# MCU_STM32L051.net
KiCad netlist of a schematic drawn in Altium Designer
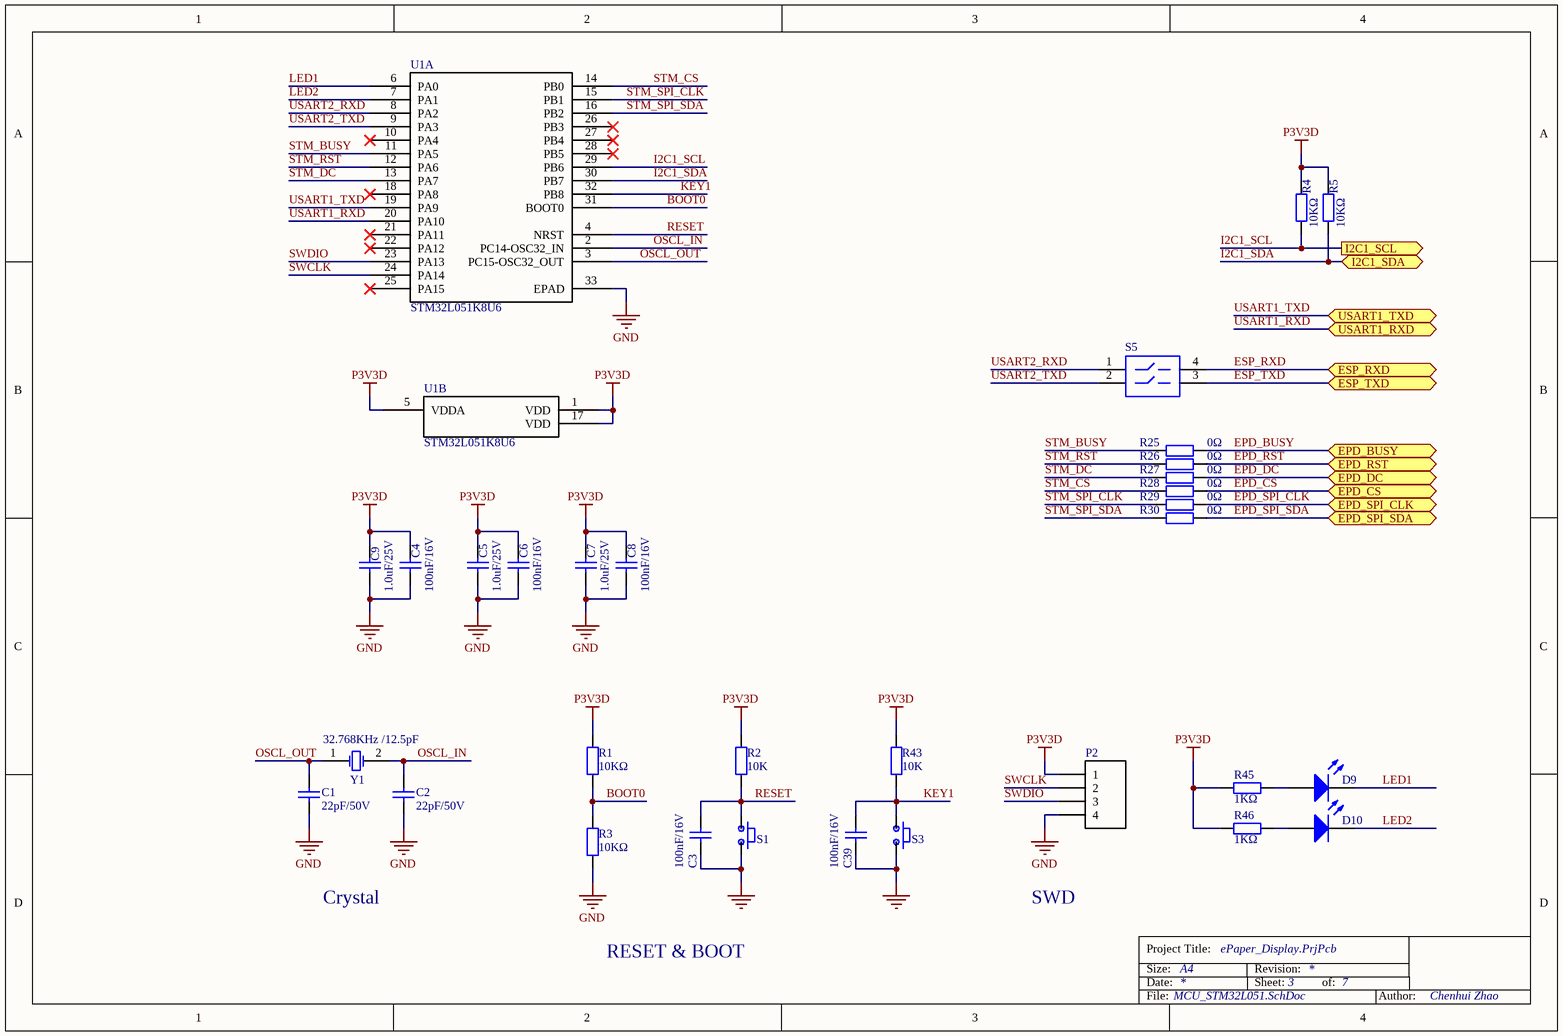
[diagram p0: MCU_STM32L051.SchDoc]

(export (version "E")
  (design (tool "Eeschema 10.0.6"))
  (components
    (comp (ref "C1")
      (value "22pF/50V")
      (footprint "0402_C")
      (description "贴片电容")
      (libsource (lib "Miscellaneous Devices LC") (part "0402 22pF (220) 5% 50V"))
    )
    (comp (ref "C2")
      (value "22pF/50V")
      (footprint "0402_C")
      (description "贴片电容")
      (libsource (lib "Miscellaneous Devices LC") (part "0402 22pF (220) 5% 50V"))
    )
    (comp (ref "C3")
      (value "100nF/16V")
      (footprint "0402_C")
      (description "贴片电容")
      (libsource (lib "Miscellaneous Devices LC") (part "0402 100nF (104) 10% 16V"))
    )
    (comp (ref "C4")
      (value "100nF/16V")
      (footprint "0402_C")
      (description "贴片电容")
      (libsource (lib "Miscellaneous Devices LC") (part "0402 100nF (104) 10% 16V"))
    )
    (comp (ref "C5")
      (value "1.0uF/25V")
      (footprint "0402_C")
      (description "贴片电容")
      (libsource (lib "Miscellaneous Devices LC") (part "0402 1.0uF (105) 10% 25V"))
    )
    (comp (ref "C6")
      (value "100nF/16V")
      (footprint "0402_C")
      (description "贴片电容")
      (libsource (lib "Miscellaneous Devices LC") (part "0402 100nF (104) 10% 16V"))
    )
    (comp (ref "C7")
      (value "1.0uF/25V")
      (footprint "0402_C")
      (description "贴片电容")
      (libsource (lib "Miscellaneous Devices LC") (part "0402 1.0uF (105) 10% 25V"))
    )
    (comp (ref "C8")
      (value "100nF/16V")
      (footprint "0402_C")
      (description "贴片电容")
      (libsource (lib "Miscellaneous Devices LC") (part "0402 100nF (104) 10% 16V"))
    )
    (comp (ref "C9")
      (value "1.0uF/25V")
      (footprint "0402_C")
      (description "贴片电容")
      (libsource (lib "Miscellaneous Devices LC") (part "0402 1.0uF (105) 10% 25V"))
    )
    (comp (ref "C39")
      (value "100nF/16V")
      (footprint "0402_C")
      (description "贴片电容")
      (libsource (lib "Miscellaneous Devices LC") (part "0402 100nF (104) 10% 16V"))
    )
    (comp (ref "D9")
      (value "蓝灯 0603")
      (footprint "0603_LED_S1")
      (description "发光二极管")
      (libsource (lib "Miscellaneous Devices LC") (part "0603 蓝灯"))
    )
    (comp (ref "D10")
      (value "蓝灯 0603")
      (footprint "0603_LED_S1")
      (description "发光二极管")
      (libsource (lib "Miscellaneous Devices LC") (part "0603 蓝灯"))
    )
    (comp (ref "P2")
      (value "Header 4")
      (footprint "DIP4-2.00")
      (description "Header, 4-Pin")
      (fields (field (name "PUBLISHER") "Altium Limited"))
      (libsource (lib "Connectors") (part "Header 4"))
    )
    (comp (ref "R1")
      (value "10KΩ")
      (footprint "0402_R")
      (description "贴片电阻")
      (libsource (lib "Miscellaneous Devices LC") (part "0402 10KΩ (1002) 1%"))
    )
    (comp (ref "R2")
      (value "10K")
      (footprint "0402_R")
      (description "贴片电阻")
      (libsource (lib "Miscellaneous Devices LC") (part "0402 10KΩ (1002) 1%"))
    )
    (comp (ref "R3")
      (value "10KΩ")
      (footprint "0402_R")
      (description "贴片电阻")
      (libsource (lib "Miscellaneous Devices LC") (part "0402 10KΩ (1002) 1%"))
    )
    (comp (ref "R4")
      (value "10KΩ")
      (footprint "0402_R")
      (description "贴片电阻")
      (libsource (lib "Miscellaneous Devices LC") (part "0402 10KΩ (1002) 1%"))
    )
    (comp (ref "R5")
      (value "10KΩ")
      (footprint "0402_R")
      (description "贴片电阻")
      (libsource (lib "Miscellaneous Devices LC") (part "0402 10KΩ (1002) 1%"))
    )
    (comp (ref "R25")
      (value "0Ω")
      (footprint "0402_R")
      (description "贴片电阻")
      (libsource (lib "Miscellaneous Devices LC") (part "0402 0Ω (0R0) 1%"))
    )
    (comp (ref "R26")
      (value "0Ω")
      (footprint "0402_R")
      (description "贴片电阻")
      (libsource (lib "Miscellaneous Devices LC") (part "0402 0Ω (0R0) 1%"))
    )
    (comp (ref "R27")
      (value "0Ω")
      (footprint "0402_R")
      (description "贴片电阻")
      (libsource (lib "Miscellaneous Devices LC") (part "0402 0Ω (0R0) 1%"))
    )
    (comp (ref "R28")
      (value "0Ω")
      (footprint "0402_R")
      (description "贴片电阻")
      (libsource (lib "Miscellaneous Devices LC") (part "0402 0Ω (0R0) 1%"))
    )
    (comp (ref "R29")
      (value "0Ω")
      (footprint "0402_R")
      (description "贴片电阻")
      (libsource (lib "Miscellaneous Devices LC") (part "0402 0Ω (0R0) 1%"))
    )
    (comp (ref "R30")
      (value "0Ω")
      (footprint "0402_R")
      (description "贴片电阻")
      (libsource (lib "Miscellaneous Devices LC") (part "0402 0Ω (0R0) 1%"))
    )
    (comp (ref "R43")
      (value "10K")
      (footprint "0402_R")
      (description "贴片电阻")
      (libsource (lib "Miscellaneous Devices LC") (part "0402 10KΩ (1002) 1%"))
    )
    (comp (ref "R45")
      (value "1KΩ")
      (footprint "0402_R")
      (description "贴片电阻")
      (libsource (lib "Miscellaneous Devices LC") (part "0402 1KΩ (1001) 1%"))
    )
    (comp (ref "R46")
      (value "1KΩ")
      (footprint "0402_R")
      (description "贴片电阻")
      (libsource (lib "Miscellaneous Devices LC") (part "0402 1KΩ (1001) 1%"))
    )
    (comp (ref "S1") (value "Button") (footprint "SKRKAHE020") (libsource (lib "Connectors") (part "Button")))
    (comp (ref "S3") (value "Button") (footprint "SKRKAHE020") (libsource (lib "Connectors") (part "Button")))
    (comp (ref "S5")
      (value "拨码开关")
      (footprint "SW_SMT4")
      (description "SMT Switch, 4 Position, SPST")
      (libsource (lib "Connectors") (part "SW-SMT2"))
    )
    (comp (ref "U1")
      (value "STM32L051K8U6")
      (footprint "UFQFPN32-5x5mm")
      (description "Ultra-low-power Arm Cortex-M0+ MCU with 64 Kbytes of Flash memory, 32 MHz CPU")
      (fields (field (name "COPYRIGHT") "Copyright (C) 2018 Accelerated Designs. All rights reserved"))
      (libsource (lib "IC") (part "STM32L051K8U6"))
    )
    (comp (ref "Y1")
      (value "32.768KHz /12.5pF")
      (footprint "SMD-3215_2P FC - 135")
      (description "贴片晶振")
      (libsource (lib "Miscellaneous Devices LC") (part "SMD-3215_2P 32.768KHz 20ppm 12.5pF"))
    )
  )
  (nets
    (net (code "1") (name "/BOOT0") (class "Default")
      (node (ref "R1") (pin "1") (pinfunction "1_1") (pintype "passive"))
      (node (ref "R3") (pin "2") (pinfunction "2_2") (pintype "passive"))
      (node (ref "U1") (pin "31") (pinfunction "BOOT0_31") (pintype "passive"))
    )
    (net (code "2") (name "/EPD_BUSY") (class "Default")
      (node (ref "R25") (pin "2") (pinfunction "2_2") (pintype "passive"))
    )
    (net (code "3") (name "/EPD_CS") (class "Default")
      (node (ref "R28") (pin "2") (pinfunction "2_2") (pintype "passive"))
    )
    (net (code "4") (name "/EPD_DC") (class "Default")
      (node (ref "R27") (pin "2") (pinfunction "2_2") (pintype "passive"))
    )
    (net (code "5") (name "/EPD_RST") (class "Default")
      (node (ref "R26") (pin "2") (pinfunction "2_2") (pintype "passive"))
    )
    (net (code "6") (name "/EPD_SPI_CLK") (class "Default")
      (node (ref "R29") (pin "2") (pinfunction "2_2") (pintype "passive"))
    )
    (net (code "7") (name "/EPD_SPI_SDA") (class "Default")
      (node (ref "R30") (pin "2") (pinfunction "2_2") (pintype "passive"))
    )
    (net (code "8") (name "/ESP_RXD") (class "Default")
      (node (ref "S5") (pin "4") (pinfunction "4_4") (pintype "passive"))
    )
    (net (code "9") (name "/ESP_TXD") (class "Default")
      (node (ref "S5") (pin "3") (pinfunction "3_3") (pintype "passive"))
    )
    (net (code "10") (name "/I2C1_SCL") (class "Default")
      (node (ref "R4") (pin "1") (pinfunction "1_1") (pintype "passive"))
      (node (ref "U1") (pin "29") (pinfunction "PB6_29") (pintype "passive"))
    )
    (net (code "11") (name "/I2C1_SDA") (class "Default")
      (node (ref "R5") (pin "1") (pinfunction "1_1") (pintype "passive"))
      (node (ref "U1") (pin "30") (pinfunction "PB7_30") (pintype "passive"))
    )
    (net (code "12") (name "/KEY1") (class "Default")
      (node (ref "C39") (pin "2") (pinfunction "2_2") (pintype "passive"))
      (node (ref "R43") (pin "1") (pinfunction "1_1") (pintype "passive"))
      (node (ref "S3") (pin "1") (pinfunction "1_1") (pintype "passive"))
      (node (ref "U1") (pin "32") (pinfunction "PB8_32") (pintype "passive"))
    )
    (net (code "13") (name "/LED1") (class "Default")
      (node (ref "D9") (pin "K") (pinfunction "K_K") (pintype "passive"))
      (node (ref "U1") (pin "6") (pinfunction "PA0_6") (pintype "passive"))
    )
    (net (code "14") (name "/LED2") (class "Default")
      (node (ref "D10") (pin "K") (pinfunction "K_K") (pintype "passive"))
      (node (ref "U1") (pin "7") (pinfunction "PA1_7") (pintype "passive"))
    )
    (net (code "15") (name "/OSCL_IN") (class "Default")
      (node (ref "C2") (pin "2") (pinfunction "2_2") (pintype "passive"))
      (node (ref "U1") (pin "2") (pinfunction "PC14-OSC32_IN_2") (pintype "passive"))
      (node (ref "Y1") (pin "2") (pinfunction "OSC2_2") (pintype "passive"))
    )
    (net (code "16") (name "/OSCL_OUT") (class "Default")
      (node (ref "C1") (pin "2") (pinfunction "2_2") (pintype "passive"))
      (node (ref "U1") (pin "3") (pinfunction "PC15-OSC32_OUT_3") (pintype "passive"))
      (node (ref "Y1") (pin "1") (pinfunction "OSC1_1") (pintype "passive"))
    )
    (net (code "17") (name "/RESET") (class "Default")
      (node (ref "C3") (pin "2") (pinfunction "2_2") (pintype "passive"))
      (node (ref "R2") (pin "1") (pinfunction "1_1") (pintype "passive"))
      (node (ref "S1") (pin "1") (pinfunction "1_1") (pintype "passive"))
      (node (ref "U1") (pin "4") (pinfunction "NRST_4") (pintype "passive"))
    )
    (net (code "18") (name "/STM_BUSY") (class "Default")
      (node (ref "R25") (pin "1") (pinfunction "1_1") (pintype "passive"))
      (node (ref "U1") (pin "11") (pinfunction "PA5_11") (pintype "passive"))
    )
    (net (code "19") (name "/STM_CS") (class "Default")
      (node (ref "R28") (pin "1") (pinfunction "1_1") (pintype "passive"))
      (node (ref "U1") (pin "14") (pinfunction "PB0_14") (pintype "passive"))
    )
    (net (code "20") (name "/STM_DC") (class "Default")
      (node (ref "R27") (pin "1") (pinfunction "1_1") (pintype "passive"))
      (node (ref "U1") (pin "13") (pinfunction "PA7_13") (pintype "passive"))
    )
    (net (code "21") (name "/STM_RST") (class "Default")
      (node (ref "R26") (pin "1") (pinfunction "1_1") (pintype "passive"))
      (node (ref "U1") (pin "12") (pinfunction "PA6_12") (pintype "passive"))
    )
    (net (code "22") (name "/STM_SPI_CLK") (class "Default")
      (node (ref "R29") (pin "1") (pinfunction "1_1") (pintype "passive"))
      (node (ref "U1") (pin "15") (pinfunction "PB1_15") (pintype "passive"))
    )
    (net (code "23") (name "/STM_SPI_SDA") (class "Default")
      (node (ref "R30") (pin "1") (pinfunction "1_1") (pintype "passive"))
      (node (ref "U1") (pin "16") (pinfunction "PB2_16") (pintype "passive"))
    )
    (net (code "24") (name "/SWCLK") (class "Default")
      (node (ref "P2") (pin "2") (pinfunction "2_2") (pintype "passive"))
      (node (ref "U1") (pin "24") (pinfunction "PA14_24") (pintype "passive"))
    )
    (net (code "25") (name "/SWDIO") (class "Default")
      (node (ref "P2") (pin "3") (pinfunction "3_3") (pintype "passive"))
      (node (ref "U1") (pin "23") (pinfunction "PA13_23") (pintype "passive"))
    )
    (net (code "26") (name "/USART1_RXD") (class "Default")
      (node (ref "U1") (pin "20") (pinfunction "PA10_20") (pintype "passive"))
    )
    (net (code "27") (name "/USART1_TXD") (class "Default")
      (node (ref "U1") (pin "19") (pinfunction "PA9_19") (pintype "passive"))
    )
    (net (code "28") (name "/USART2_RXD") (class "Default")
      (node (ref "S5") (pin "1") (pinfunction "1_1") (pintype "passive"))
      (node (ref "U1") (pin "8") (pinfunction "PA2_8") (pintype "passive"))
    )
    (net (code "29") (name "/USART2_TXD") (class "Default")
      (node (ref "S5") (pin "2") (pinfunction "2_2") (pintype "passive"))
      (node (ref "U1") (pin "9") (pinfunction "PA3_9") (pintype "passive"))
    )
    (net (code "30") (name "GND") (class "Default")
      (node (ref "C1") (pin "1") (pinfunction "1_1") (pintype "passive"))
      (node (ref "C2") (pin "1") (pinfunction "1_1") (pintype "passive"))
      (node (ref "C3") (pin "1") (pinfunction "1_1") (pintype "passive"))
      (node (ref "C39") (pin "1") (pinfunction "1_1") (pintype "passive"))
      (node (ref "C4") (pin "1") (pinfunction "1_1") (pintype "passive"))
      (node (ref "C5") (pin "1") (pinfunction "1_1") (pintype "passive"))
      (node (ref "C6") (pin "1") (pinfunction "1_1") (pintype "passive"))
      (node (ref "C7") (pin "1") (pinfunction "1_1") (pintype "passive"))
      (node (ref "C8") (pin "1") (pinfunction "1_1") (pintype "passive"))
      (node (ref "C9") (pin "1") (pinfunction "1_1") (pintype "passive"))
      (node (ref "P2") (pin "4") (pinfunction "4_4") (pintype "passive"))
      (node (ref "R3") (pin "1") (pinfunction "1_1") (pintype "passive"))
      (node (ref "S1") (pin "2") (pinfunction "2_2") (pintype "passive"))
      (node (ref "S3") (pin "2") (pinfunction "2_2") (pintype "passive"))
      (node (ref "U1") (pin "33") (pinfunction "EPAD_33") (pintype "passive"))
    )
    (net (code "31") (name "Net-(D9-PadA)") (class "Default")
      (node (ref "D9") (pin "A") (pinfunction "A_A") (pintype "passive"))
      (node (ref "R45") (pin "1") (pinfunction "1_1") (pintype "passive"))
    )
    (net (code "32") (name "Net-(D10-PadA)") (class "Default")
      (node (ref "D10") (pin "A") (pinfunction "A_A") (pintype "passive"))
      (node (ref "R46") (pin "1") (pinfunction "1_1") (pintype "passive"))
    )
    (net (code "33") (name "P3V3D") (class "Default")
      (node (ref "C4") (pin "2") (pinfunction "2_2") (pintype "passive"))
      (node (ref "C5") (pin "2") (pinfunction "2_2") (pintype "passive"))
      (node (ref "C6") (pin "2") (pinfunction "2_2") (pintype "passive"))
      (node (ref "C7") (pin "2") (pinfunction "2_2") (pintype "passive"))
      (node (ref "C8") (pin "2") (pinfunction "2_2") (pintype "passive"))
      (node (ref "C9") (pin "2") (pinfunction "2_2") (pintype "passive"))
      (node (ref "P2") (pin "1") (pinfunction "1_1") (pintype "passive"))
      (node (ref "R1") (pin "2") (pinfunction "2_2") (pintype "passive"))
      (node (ref "R2") (pin "2") (pinfunction "2_2") (pintype "passive"))
      (node (ref "R4") (pin "2") (pinfunction "2_2") (pintype "passive"))
      (node (ref "R43") (pin "2") (pinfunction "2_2") (pintype "passive"))
      (node (ref "R45") (pin "2") (pinfunction "2_2") (pintype "passive"))
      (node (ref "R46") (pin "2") (pinfunction "2_2") (pintype "passive"))
      (node (ref "R5") (pin "2") (pinfunction "2_2") (pintype "passive"))
      (node (ref "U1") (pin "1") (pinfunction "VDD_1") (pintype "power_in"))
      (node (ref "U1") (pin "17") (pinfunction "VDD_17") (pintype "power_in"))
      (node (ref "U1") (pin "5") (pinfunction "VDDA_5") (pintype "power_in"))
    )
    (net (code "34") (name "unconnected-(U1A-PA4-Pad10)") (class "Default")
      (node (ref "U1") (pin "10") (pinfunction "PA4_10") (pintype "passive+no_connect"))
    )
    (net (code "35") (name "unconnected-(U1A-PA8-Pad18)") (class "Default")
      (node (ref "U1") (pin "18") (pinfunction "PA8_18") (pintype "passive+no_connect"))
    )
    (net (code "36") (name "unconnected-(U1A-PA11-Pad21)") (class "Default")
      (node (ref "U1") (pin "21") (pinfunction "PA11_21") (pintype "passive+no_connect"))
    )
    (net (code "37") (name "unconnected-(U1A-PA12-Pad22)") (class "Default")
      (node (ref "U1") (pin "22") (pinfunction "PA12_22") (pintype "passive+no_connect"))
    )
    (net (code "38") (name "unconnected-(U1A-PA15-Pad25)") (class "Default")
      (node (ref "U1") (pin "25") (pinfunction "PA15_25") (pintype "passive+no_connect"))
    )
    (net (code "39") (name "unconnected-(U1A-PB3-Pad26)") (class "Default")
      (node (ref "U1") (pin "26") (pinfunction "PB3_26") (pintype "passive+no_connect"))
    )
    (net (code "40") (name "unconnected-(U1A-PB4-Pad27)") (class "Default")
      (node (ref "U1") (pin "27") (pinfunction "PB4_27") (pintype "passive+no_connect"))
    )
    (net (code "41") (name "unconnected-(U1A-PB5-Pad28)") (class "Default")
      (node (ref "U1") (pin "28") (pinfunction "PB5_28") (pintype "passive+no_connect"))
    )
  )
)
